# Stepper_Tester.net
KiCad netlist of a schematic drawn in EAGLE
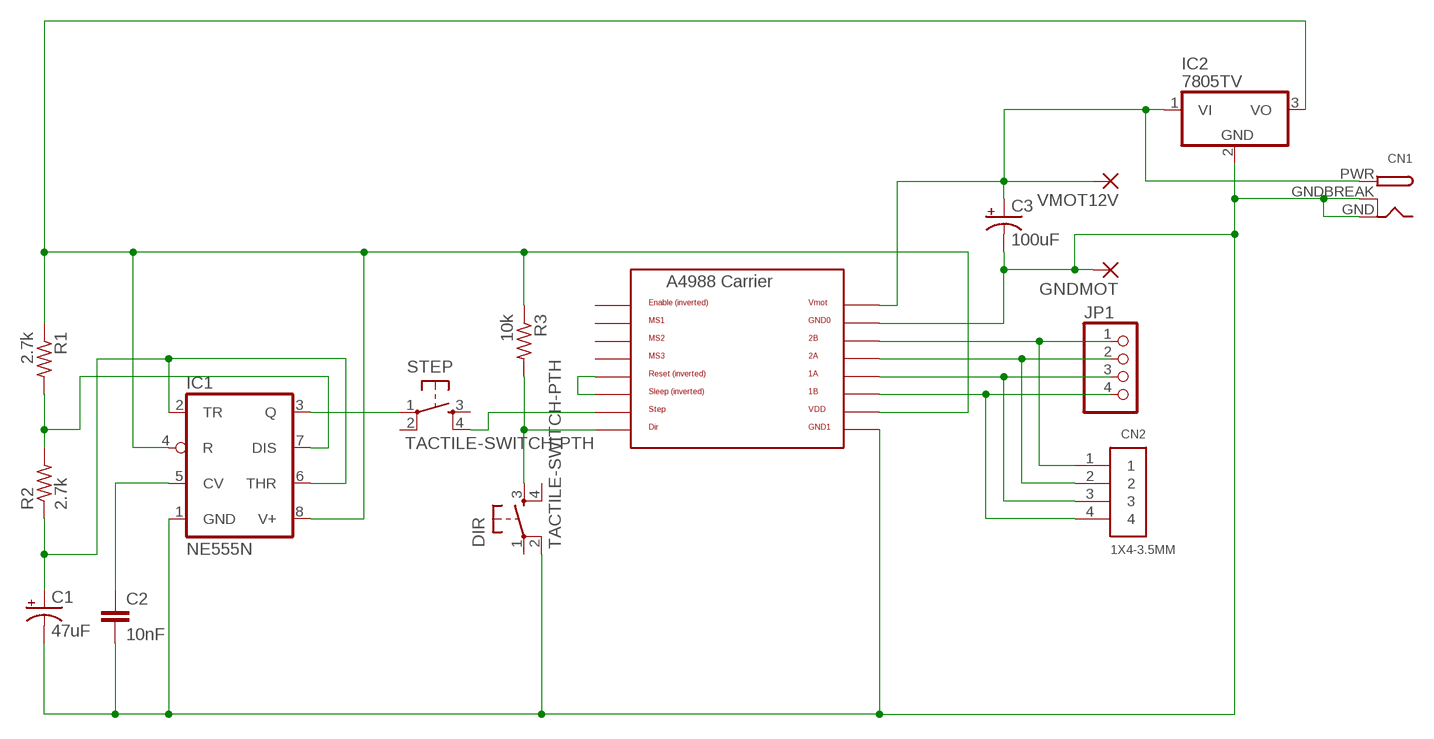
[diagram p0: schematic, sheet 1]

(export (version "E")
  (design (tool "Eeschema 10.0.6"))
  (components
    (comp (ref "C1")
      (value "47uF")
      (footprint "eagle-import:B45181B")
      (libsource (lib "eagle-import") (part "CPOL-USB45181B"))
    )
    (comp (ref "C2")
      (value "10nF")
      (footprint "eagle-import:C050-024X044")
      (libsource (lib "eagle-import") (part "C-EU050-024X044"))
    )
    (comp (ref "C3")
      (value "100uF")
      (footprint "eagle-import:E3,5-10")
      (libsource (lib "eagle-import") (part "CPOL-USE3.5-10"))
    )
    (comp (ref "CN1")
      (value "DCBARRELPTH")
      (footprint "eagle-import:DCJACK_2MM_PTH")
      (libsource (lib "eagle-import") (part "DCBARRELPTH"))
    )
    (comp (ref "CN2")
      (value "1X4-3.5MM")
      (footprint "eagle-import:1X04-3.5MM")
      (libsource (lib "eagle-import") (part "1X4-3.5MM"))
    )
    (comp (ref "DIR")
      (value "TACTILE-SWITCH-PTH")
      (footprint "eagle-import:TAC-SWITCH-PTH")
      (libsource (lib "eagle-import") (part "TACTILE-SWITCH-PTH"))
    )
    (comp (ref "GNDMOT")
      (value "3,81/1,4")
      (footprint "eagle-import:3,81_1,4")
      (libsource (lib "eagle-import") (part "3,81/1,4"))
    )
    (comp (ref "IC1")
      (value "NE555N")
      (footprint "eagle-import:DIL08-ROUND")
      (libsource (lib "eagle-import") (part "555NNE"))
    )
    (comp (ref "IC2")
      (value "7805TV")
      (footprint "eagle-import:TO220V")
      (libsource (lib "eagle-import") (part "78TV05"))
    )
    (comp (ref "JP1")
      (value "PINHD-1X4")
      (footprint "eagle-import:1X04")
      (libsource (lib "eagle-import") (part "PINHD-1X4"))
    )
    (comp (ref "R1")
      (value "2.7k")
      (footprint "eagle-import:0414_15")
      (libsource (lib "eagle-import") (part "R-US_0414/15"))
    )
    (comp (ref "R2")
      (value "2.7k")
      (footprint "eagle-import:0414_15")
      (libsource (lib "eagle-import") (part "R-US_0414/15"))
    )
    (comp (ref "R3")
      (value "10k")
      (footprint "eagle-import:0414_15")
      (libsource (lib "eagle-import") (part "R-US_0414/15"))
    )
    (comp (ref "STEP")
      (value "TACTILE-SWITCH-PTH")
      (footprint "eagle-import:TAC-SWITCH-PTH")
      (libsource (lib "eagle-import") (part "TACTILE-SWITCH-PTH"))
    )
    (comp (ref "U$1")
      (value "A4983CARRIER")
      (footprint "eagle-import:A4988BREAKOUT")
      (libsource (lib "eagle-import") (part "A4983CARRIER"))
    )
    (comp (ref "VMOT12V")
      (value "3,81/1,4")
      (footprint "eagle-import:3,81_1,4")
      (libsource (lib "eagle-import") (part "3,81/1,4"))
    )
  )
  (nets
    (net (code "1") (name "Net-(CN2-Pad1)") (class "Default")
      (node (ref "CN2") (pin "1") (pinfunction "1_1") (pintype "bidirectional"))
      (node (ref "JP1") (pin "1") (pinfunction "1_1") (pintype "passive"))
      (node (ref "U$1") (pin "2B") (pinfunction "2B_2B") (pintype "output"))
    )
    (net (code "2") (name "Net-(CN2-Pad2)") (class "Default")
      (node (ref "CN2") (pin "2") (pinfunction "2_2") (pintype "bidirectional"))
      (node (ref "JP1") (pin "2") (pinfunction "2_2") (pintype "passive"))
      (node (ref "U$1") (pin "2A") (pinfunction "2A_2A") (pintype "output"))
    )
    (net (code "3") (name "Net-(CN2-Pad3)") (class "Default")
      (node (ref "CN2") (pin "3") (pinfunction "3_3") (pintype "bidirectional"))
      (node (ref "JP1") (pin "3") (pinfunction "3_3") (pintype "passive"))
      (node (ref "U$1") (pin "1A") (pinfunction "1A_1A") (pintype "output"))
    )
    (net (code "4") (name "Net-(CN2-Pad4)") (class "Default")
      (node (ref "CN2") (pin "4") (pinfunction "4_4") (pintype "bidirectional"))
      (node (ref "JP1") (pin "4") (pinfunction "4_4") (pintype "passive"))
      (node (ref "U$1") (pin "1B") (pinfunction "1B_1B") (pintype "output"))
    )
    (net (code "5") (name "Net-(DIR-Pad3)") (class "Default")
      (node (ref "DIR") (pin "3") (pinfunction "3_3") (pintype "passive"))
      (node (ref "R3") (pin "2") (pinfunction "2_2") (pintype "passive"))
      (node (ref "U$1") (pin "DIR") (pinfunction "DIR_DIR") (pintype "input"))
    )
    (net (code "6") (name "Net-(GNDMOT-P)") (class "Default")
      (node (ref "C1") (pin "-") (pinfunction "-_-") (pintype "passive"))
      (node (ref "C2") (pin "2") (pinfunction "2_2") (pintype "passive"))
      (node (ref "C3") (pin "-") (pinfunction "-_-") (pintype "passive"))
      (node (ref "CN1") (pin "GND") (pinfunction "GND_GND") (pintype "power_in"))
      (node (ref "CN1") (pin "GNDBREAK") (pinfunction "GNDBREAK_GNDBREAK") (pintype "power_in"))
      (node (ref "DIR") (pin "2") (pinfunction "2_2") (pintype "passive"))
      (node (ref "GNDMOT") (pin "1") (pinfunction "P_1") (pintype "passive"))
      (node (ref "IC1") (pin "1") (pinfunction "GND_1") (pintype "power_in"))
      (node (ref "IC2") (pin "2") (pinfunction "GND_2") (pintype "passive"))
      (node (ref "U$1") (pin "GND0") (pinfunction "GND0_GND0") (pintype "power_in"))
      (node (ref "U$1") (pin "GND1") (pinfunction "GND1_GND1") (pintype "power_in"))
    )
    (net (code "7") (name "Net-(IC1-CV)") (class "Default")
      (node (ref "C2") (pin "1") (pinfunction "1_1") (pintype "passive"))
      (node (ref "IC1") (pin "5") (pinfunction "CV_5") (pintype "input"))
    )
    (net (code "8") (name "Net-(IC1-DIS)") (class "Default")
      (node (ref "IC1") (pin "7") (pinfunction "DIS_7") (pintype "input"))
      (node (ref "R1") (pin "2") (pinfunction "2_2") (pintype "passive"))
      (node (ref "R2") (pin "2") (pinfunction "2_2") (pintype "passive"))
    )
    (net (code "9") (name "Net-(IC1-Q)") (class "Default")
      (node (ref "IC1") (pin "3") (pinfunction "Q_3") (pintype "output"))
      (node (ref "STEP") (pin "1") (pinfunction "1_1") (pintype "passive"))
    )
    (net (code "10") (name "Net-(IC1-R)") (class "Default")
      (node (ref "IC1") (pin "4") (pinfunction "R_4") (pintype "input"))
      (node (ref "IC1") (pin "8") (pinfunction "V+_8") (pintype "power_in"))
      (node (ref "IC2") (pin "3") (pinfunction "VO_3") (pintype "passive"))
      (node (ref "R1") (pin "1") (pinfunction "1_1") (pintype "passive"))
      (node (ref "R3") (pin "1") (pinfunction "1_1") (pintype "passive"))
      (node (ref "U$1") (pin "VDD") (pinfunction "VDD_VDD") (pintype "power_in"))
    )
    (net (code "11") (name "Net-(IC1-THR)") (class "Default")
      (node (ref "C1") (pin "+") (pinfunction "+_+") (pintype "passive"))
      (node (ref "IC1") (pin "2") (pinfunction "TR_2") (pintype "input"))
      (node (ref "IC1") (pin "6") (pinfunction "THR_6") (pintype "input"))
      (node (ref "R2") (pin "1") (pinfunction "1_1") (pintype "passive"))
    )
    (net (code "12") (name "Net-(IC2-VI)") (class "Default")
      (node (ref "C3") (pin "+") (pinfunction "+_+") (pintype "passive"))
      (node (ref "CN1") (pin "PWR") (pinfunction "PWR_PWR") (pintype "power_in"))
      (node (ref "IC2") (pin "1") (pinfunction "VI_1") (pintype "input"))
      (node (ref "U$1") (pin "VMOT") (pinfunction "VMOT_VMOT") (pintype "power_in"))
      (node (ref "VMOT12V") (pin "1") (pinfunction "P_1") (pintype "passive"))
    )
    (net (code "13") (name "Net-(STEP-Pad4)") (class "Default")
      (node (ref "STEP") (pin "4") (pinfunction "4_4") (pintype "passive"))
      (node (ref "U$1") (pin "STEP") (pinfunction "STEP_STEP") (pintype "input"))
    )
    (net (code "14") (name "Net-(U$1-SLEEP)") (class "Default")
      (node (ref "U$1") (pin "RST") (pinfunction "RST_RST") (pintype "input"))
      (node (ref "U$1") (pin "SLP") (pinfunction "SLEEP_SLP") (pintype "input"))
    )
    (net (code "15") (name "unconnected-(DIR-Pad1)") (class "Default")
      (node (ref "DIR") (pin "1") (pinfunction "1_1") (pintype "passive"))
    )
    (net (code "16") (name "unconnected-(DIR-Pad4)") (class "Default")
      (node (ref "DIR") (pin "4") (pinfunction "4_4") (pintype "passive"))
    )
    (net (code "17") (name "unconnected-(STEP-Pad2)") (class "Default")
      (node (ref "STEP") (pin "2") (pinfunction "2_2") (pintype "passive"))
    )
    (net (code "18") (name "unconnected-(STEP-Pad3)") (class "Default")
      (node (ref "STEP") (pin "3") (pinfunction "3_3") (pintype "passive"))
    )
    (net (code "19") (name "unconnected-(U$1-PadEN)") (class "Default")
      (node (ref "U$1") (pin "EN") (pinfunction "EN_EN") (pintype "input"))
    )
    (net (code "20") (name "unconnected-(U$1-PadMS1)") (class "Default")
      (node (ref "U$1") (pin "MS1") (pinfunction "MS1_MS1") (pintype "input"))
    )
    (net (code "21") (name "unconnected-(U$1-PadMS2)") (class "Default")
      (node (ref "U$1") (pin "MS2") (pinfunction "MS2_MS2") (pintype "input"))
    )
    (net (code "22") (name "unconnected-(U$1-PadMS3)") (class "Default")
      (node (ref "U$1") (pin "MS3") (pinfunction "MS3_MS3") (pintype "input"))
    )
  )
)
